# Bus_and_display.net
KiCad netlist of a schematic drawn in Altium Designer
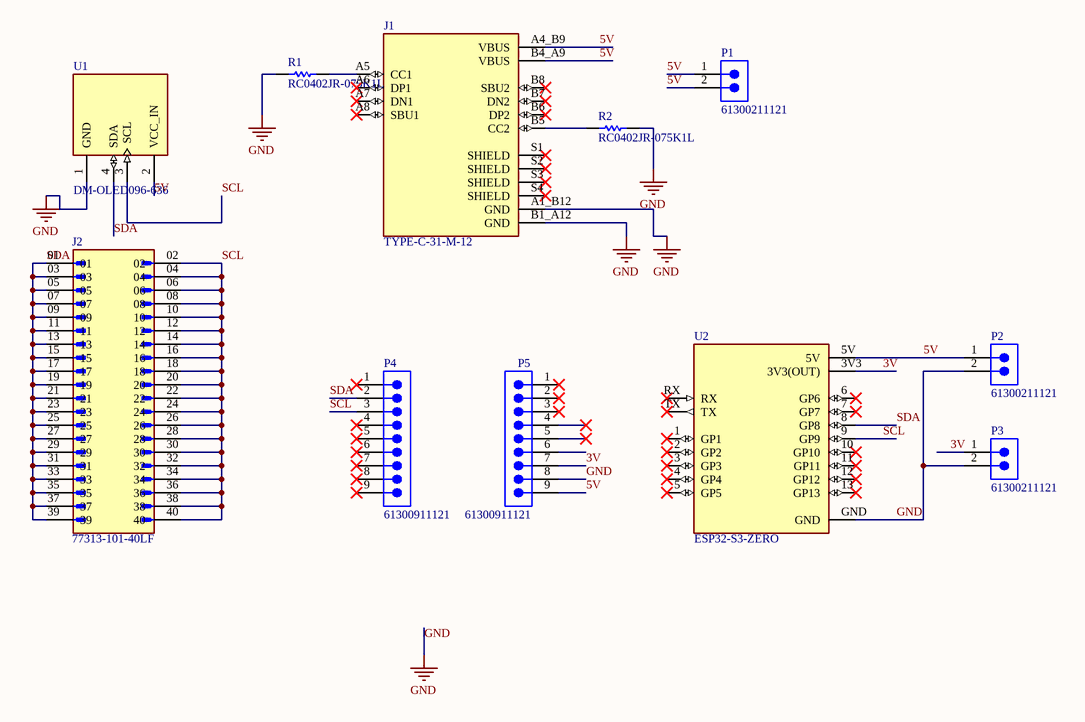
[diagram p0: Bus_and_display.SchDoc]

(export (version "E")
  (design (tool "Eeschema 10.0.6"))
  (components
    (comp (ref "J1")
      (value "TYPE-C-31-M-12")
      (footprint "HRO_TYPE-C-31-M-12")
      (description "USB Connectors 24 Receptacle 1 8.94*7.3mm RoHS")
      (fields (field (name "MF") "HRO Electronics Co., Ltd."))
      (libsource (lib "TYPE-C-31-M-12") (part "TYPE-C-31-M-12"))
    )
    (comp (ref "J2")
      (value "77313-101-40LF")
      (footprint "AMPHENOL_77313-101-40LF")
      (fields (field (name "MF") "Amphenol"))
      (libsource (lib "77313-101-40LF") (part "77313-101-40LF"))
    )
    (comp (ref "P1")
      (value "61300211121")
      (footprint "61300211121")
      (description "THT Vertical Pin Header WR-PHD, Pitch 2.54 mm, Single Row, 2 pins")
      (libsource (lib "Altium Content Vault") (part "Header_Male_1R_02P"))
    )
    (comp (ref "P2")
      (value "61300211121")
      (footprint "61300211121")
      (description "THT Vertical Pin Header WR-PHD, Pitch 2.54 mm, Single Row, 2 pins")
      (libsource (lib "Altium Content Vault") (part "Header_Male_1R_02P"))
    )
    (comp (ref "P3")
      (value "61300211121")
      (footprint "61300211121")
      (description "THT Vertical Pin Header WR-PHD, Pitch 2.54 mm, Single Row, 2 pins")
      (libsource (lib "Altium Content Vault") (part "Header_Male_1R_02P"))
    )
    (comp (ref "P4")
      (value "61300911121")
      (footprint "61300911121")
      (description "THT Vertical Pin Header WR-PHD, Pitch 2.54 mm, Single Row, 9 pins")
      (libsource (lib "Altium Content Vault") (part "Header_Male_1R_09P"))
    )
    (comp (ref "P5")
      (value "61300911121")
      (footprint "61300911121")
      (description "THT Vertical Pin Header WR-PHD, Pitch 2.54 mm, Single Row, 9 pins")
      (libsource (lib "Altium Content Vault") (part "Header_Male_1R_09P"))
    )
    (comp (ref "R1")
      (value "RC0402JR-075K1L")
      (footprint "RESC1005X40X25ML05T10")
      (fields (field (name "MANUFACTURER") "Yageo / Phycomp"))
      (libsource (lib "Altium Content Vault") (part "RES"))
    )
    (comp (ref "R2")
      (value "RC0402JR-075K1L")
      (footprint "RESC1005X40X25ML05T10")
      (fields (field (name "MANUFACTURER") "Yageo / Phycomp"))
      (libsource (lib "Altium Content Vault") (part "RES"))
    )
    (comp (ref "U1")
      (value "DM-OLED096-636")
      (footprint "MODULE_DM-OLED096-636")
      (description "0.96â€ 128 X 64 MONOCHROME GRAPHIC OLED DISPLAY MODULE - I2C")
      (fields (field (name "MF") "Display Module"))
      (libsource (lib "DM-OLED096-636") (part "DM-OLED096-636"))
    )
    (comp (ref "U2")
      (value "ESP32-S3-ZERO")
      (footprint "MODULE_ESP32-S3-ZERO")
      (fields (field (name "MF") "Waveshare Electronics") (field (name "MP") "ESP32-S3-Zero"))
      (libsource (lib "ESP32-S3-ZERO") (part "ESP32-S3-ZERO"))
    )
  )
  (nets
    (net (code "1") (name "/3V") (class "Default")
      (node (ref "P3") (pin "1") (pinfunction "1_1") (pintype "passive"))
      (node (ref "P5") (pin "7") (pinfunction "7_7") (pintype "passive"))
      (node (ref "U2") (pin "3V3") (pinfunction "3V3(OUT)_3V3") (pintype "power_in"))
    )
    (net (code "2") (name "/5V") (class "Default")
      (node (ref "J1") (pin "A4_B9") (pinfunction "VBUS_A4_B9") (pintype "power_in"))
      (node (ref "J1") (pin "B4_A9") (pinfunction "VBUS_B4_A9") (pintype "power_in"))
      (node (ref "P1") (pin "1") (pinfunction "1_1") (pintype "passive"))
      (node (ref "P1") (pin "2") (pinfunction "2_2") (pintype "passive"))
      (node (ref "P2") (pin "1") (pinfunction "1_1") (pintype "passive"))
      (node (ref "P5") (pin "9") (pinfunction "9_9") (pintype "passive"))
      (node (ref "U1") (pin "2") (pinfunction "VCC_IN_2") (pintype "power_in"))
      (node (ref "U2") (pin "5V") (pinfunction "5V_5V") (pintype "power_in"))
    )
    (net (code "3") (name "/SCL") (class "Default")
      (node (ref "J2") (pin "02") (pinfunction "02_02") (pintype "passive"))
      (node (ref "J2") (pin "04") (pinfunction "04_04") (pintype "passive"))
      (node (ref "J2") (pin "06") (pinfunction "06_06") (pintype "passive"))
      (node (ref "J2") (pin "08") (pinfunction "08_08") (pintype "passive"))
      (node (ref "J2") (pin "10") (pinfunction "10_10") (pintype "passive"))
      (node (ref "J2") (pin "12") (pinfunction "12_12") (pintype "passive"))
      (node (ref "J2") (pin "14") (pinfunction "14_14") (pintype "passive"))
      (node (ref "J2") (pin "16") (pinfunction "16_16") (pintype "passive"))
      (node (ref "J2") (pin "18") (pinfunction "18_18") (pintype "passive"))
      (node (ref "J2") (pin "20") (pinfunction "20_20") (pintype "passive"))
      (node (ref "J2") (pin "22") (pinfunction "22_22") (pintype "passive"))
      (node (ref "J2") (pin "24") (pinfunction "24_24") (pintype "passive"))
      (node (ref "J2") (pin "26") (pinfunction "26_26") (pintype "passive"))
      (node (ref "J2") (pin "28") (pinfunction "28_28") (pintype "passive"))
      (node (ref "J2") (pin "30") (pinfunction "30_30") (pintype "passive"))
      (node (ref "J2") (pin "32") (pinfunction "32_32") (pintype "passive"))
      (node (ref "J2") (pin "34") (pinfunction "34_34") (pintype "passive"))
      (node (ref "J2") (pin "36") (pinfunction "36_36") (pintype "passive"))
      (node (ref "J2") (pin "38") (pinfunction "38_38") (pintype "passive"))
      (node (ref "J2") (pin "40") (pinfunction "40_40") (pintype "passive"))
      (node (ref "P4") (pin "3") (pinfunction "3_3") (pintype "passive"))
      (node (ref "U1") (pin "3") (pinfunction "SCL_3") (pintype "input"))
      (node (ref "U2") (pin "9") (pinfunction "GP9_9") (pintype "bidirectional"))
    )
    (net (code "4") (name "/SDA") (class "Default")
      (node (ref "J2") (pin "01") (pinfunction "01_01") (pintype "passive"))
      (node (ref "J2") (pin "03") (pinfunction "03_03") (pintype "passive"))
      (node (ref "J2") (pin "05") (pinfunction "05_05") (pintype "passive"))
      (node (ref "J2") (pin "07") (pinfunction "07_07") (pintype "passive"))
      (node (ref "J2") (pin "09") (pinfunction "09_09") (pintype "passive"))
      (node (ref "J2") (pin "11") (pinfunction "11_11") (pintype "passive"))
      (node (ref "J2") (pin "13") (pinfunction "13_13") (pintype "passive"))
      (node (ref "J2") (pin "15") (pinfunction "15_15") (pintype "passive"))
      (node (ref "J2") (pin "17") (pinfunction "17_17") (pintype "passive"))
      (node (ref "J2") (pin "19") (pinfunction "19_19") (pintype "passive"))
      (node (ref "J2") (pin "21") (pinfunction "21_21") (pintype "passive"))
      (node (ref "J2") (pin "23") (pinfunction "23_23") (pintype "passive"))
      (node (ref "J2") (pin "25") (pinfunction "25_25") (pintype "passive"))
      (node (ref "J2") (pin "27") (pinfunction "27_27") (pintype "passive"))
      (node (ref "J2") (pin "29") (pinfunction "29_29") (pintype "passive"))
      (node (ref "J2") (pin "31") (pinfunction "31_31") (pintype "passive"))
      (node (ref "J2") (pin "33") (pinfunction "33_33") (pintype "passive"))
      (node (ref "J2") (pin "35") (pinfunction "35_35") (pintype "passive"))
      (node (ref "J2") (pin "37") (pinfunction "37_37") (pintype "passive"))
      (node (ref "J2") (pin "39") (pinfunction "39_39") (pintype "passive"))
      (node (ref "P4") (pin "2") (pinfunction "2_2") (pintype "passive"))
      (node (ref "U1") (pin "4") (pinfunction "SDA_4") (pintype "bidirectional"))
      (node (ref "U2") (pin "8") (pinfunction "GP8_8") (pintype "bidirectional"))
    )
    (net (code "5") (name "GND") (class "Default")
      (node (ref "J1") (pin "A1_B12") (pinfunction "GND_A1_B12") (pintype "power_in"))
      (node (ref "J1") (pin "B1_A12") (pinfunction "GND_B1_A12") (pintype "power_in"))
      (node (ref "P2") (pin "2") (pinfunction "2_2") (pintype "passive"))
      (node (ref "P3") (pin "2") (pinfunction "2_2") (pintype "passive"))
      (node (ref "P5") (pin "8") (pinfunction "8_8") (pintype "passive"))
      (node (ref "R1") (pin "1") (pinfunction "1_1") (pintype "passive"))
      (node (ref "R2") (pin "2") (pinfunction "2_2") (pintype "passive"))
      (node (ref "U1") (pin "1") (pinfunction "GND_1") (pintype "power_in"))
      (node (ref "U2") (pin "GND") (pinfunction "GND_GND") (pintype "power_in"))
    )
    (net (code "6") (name "Net-(J1-CC1)") (class "Default")
      (node (ref "J1") (pin "A5") (pinfunction "CC1_A5") (pintype "bidirectional"))
      (node (ref "R1") (pin "2") (pinfunction "2_2") (pintype "passive"))
    )
    (net (code "7") (name "Net-(J1-CC2)") (class "Default")
      (node (ref "J1") (pin "B5") (pinfunction "CC2_B5") (pintype "bidirectional"))
      (node (ref "R2") (pin "1") (pinfunction "1_1") (pintype "passive"))
    )
    (net (code "8") (name "unconnected-(J1-DN1-PadA7)") (class "Default")
      (node (ref "J1") (pin "A7") (pinfunction "DN1_A7") (pintype "bidirectional+no_connect"))
    )
    (net (code "9") (name "unconnected-(J1-DN2-PadB7)") (class "Default")
      (node (ref "J1") (pin "B7") (pinfunction "DN2_B7") (pintype "bidirectional+no_connect"))
    )
    (net (code "10") (name "unconnected-(J1-DP1-PadA6)") (class "Default")
      (node (ref "J1") (pin "A6") (pinfunction "DP1_A6") (pintype "bidirectional+no_connect"))
    )
    (net (code "11") (name "unconnected-(J1-DP2-PadB6)") (class "Default")
      (node (ref "J1") (pin "B6") (pinfunction "DP2_B6") (pintype "bidirectional+no_connect"))
    )
    (net (code "12") (name "unconnected-(J1-SBU1-PadA8)") (class "Default")
      (node (ref "J1") (pin "A8") (pinfunction "SBU1_A8") (pintype "bidirectional+no_connect"))
    )
    (net (code "13") (name "unconnected-(J1-SBU2-PadB8)") (class "Default")
      (node (ref "J1") (pin "B8") (pinfunction "SBU2_B8") (pintype "bidirectional+no_connect"))
    )
    (net (code "14") (name "unconnected-(J1-SHIELD-PadS1)") (class "Default")
      (node (ref "J1") (pin "S1") (pinfunction "SHIELD_S1") (pintype "passive+no_connect"))
    )
    (net (code "15") (name "unconnected-(J1-SHIELD-PadS2)") (class "Default")
      (node (ref "J1") (pin "S2") (pinfunction "SHIELD_S2") (pintype "passive+no_connect"))
    )
    (net (code "16") (name "unconnected-(J1-SHIELD-PadS3)") (class "Default")
      (node (ref "J1") (pin "S3") (pinfunction "SHIELD_S3") (pintype "passive+no_connect"))
    )
    (net (code "17") (name "unconnected-(J1-SHIELD-PadS4)") (class "Default")
      (node (ref "J1") (pin "S4") (pinfunction "SHIELD_S4") (pintype "passive+no_connect"))
    )
    (net (code "18") (name "unconnected-(P4-Pad1)") (class "Default")
      (node (ref "P4") (pin "1") (pinfunction "1_1") (pintype "passive+no_connect"))
    )
    (net (code "19") (name "unconnected-(P4-Pad4)") (class "Default")
      (node (ref "P4") (pin "4") (pinfunction "4_4") (pintype "passive+no_connect"))
    )
    (net (code "20") (name "unconnected-(P4-Pad5)") (class "Default")
      (node (ref "P4") (pin "5") (pinfunction "5_5") (pintype "passive+no_connect"))
    )
    (net (code "21") (name "unconnected-(P4-Pad6)") (class "Default")
      (node (ref "P4") (pin "6") (pinfunction "6_6") (pintype "passive+no_connect"))
    )
    (net (code "22") (name "unconnected-(P4-Pad7)") (class "Default")
      (node (ref "P4") (pin "7") (pinfunction "7_7") (pintype "passive+no_connect"))
    )
    (net (code "23") (name "unconnected-(P4-Pad8)") (class "Default")
      (node (ref "P4") (pin "8") (pinfunction "8_8") (pintype "passive+no_connect"))
    )
    (net (code "24") (name "unconnected-(P4-Pad9)") (class "Default")
      (node (ref "P4") (pin "9") (pinfunction "9_9") (pintype "passive+no_connect"))
    )
    (net (code "25") (name "unconnected-(P5-Pad1)") (class "Default")
      (node (ref "P5") (pin "1") (pinfunction "1_1") (pintype "passive+no_connect"))
    )
    (net (code "26") (name "unconnected-(P5-Pad2)") (class "Default")
      (node (ref "P5") (pin "2") (pinfunction "2_2") (pintype "passive+no_connect"))
    )
    (net (code "27") (name "unconnected-(P5-Pad3)") (class "Default")
      (node (ref "P5") (pin "3") (pinfunction "3_3") (pintype "passive+no_connect"))
    )
    (net (code "28") (name "unconnected-(P5-Pad4)") (class "Default")
      (node (ref "P5") (pin "4") (pinfunction "4_4") (pintype "passive+no_connect"))
    )
    (net (code "29") (name "unconnected-(P5-Pad5)") (class "Default")
      (node (ref "P5") (pin "5") (pinfunction "5_5") (pintype "passive+no_connect"))
    )
    (net (code "30") (name "unconnected-(P5-Pad6)") (class "Default")
      (node (ref "P5") (pin "6") (pinfunction "6_6") (pintype "passive"))
    )
    (net (code "31") (name "unconnected-(U2-GP1-Pad1)") (class "Default")
      (node (ref "U2") (pin "1") (pinfunction "GP1_1") (pintype "bidirectional+no_connect"))
    )
    (net (code "32") (name "unconnected-(U2-GP2-Pad2)") (class "Default")
      (node (ref "U2") (pin "2") (pinfunction "GP2_2") (pintype "bidirectional+no_connect"))
    )
    (net (code "33") (name "unconnected-(U2-GP3-Pad3)") (class "Default")
      (node (ref "U2") (pin "3") (pinfunction "GP3_3") (pintype "bidirectional+no_connect"))
    )
    (net (code "34") (name "unconnected-(U2-GP4-Pad4)") (class "Default")
      (node (ref "U2") (pin "4") (pinfunction "GP4_4") (pintype "bidirectional+no_connect"))
    )
    (net (code "35") (name "unconnected-(U2-GP5-Pad5)") (class "Default")
      (node (ref "U2") (pin "5") (pinfunction "GP5_5") (pintype "bidirectional+no_connect"))
    )
    (net (code "36") (name "unconnected-(U2-GP6-Pad6)") (class "Default")
      (node (ref "U2") (pin "6") (pinfunction "GP6_6") (pintype "bidirectional+no_connect"))
    )
    (net (code "37") (name "unconnected-(U2-GP7-Pad7)") (class "Default")
      (node (ref "U2") (pin "7") (pinfunction "GP7_7") (pintype "bidirectional+no_connect"))
    )
    (net (code "38") (name "unconnected-(U2-GP10-Pad10)") (class "Default")
      (node (ref "U2") (pin "10") (pinfunction "GP10_10") (pintype "bidirectional+no_connect"))
    )
    (net (code "39") (name "unconnected-(U2-GP11-Pad11)") (class "Default")
      (node (ref "U2") (pin "11") (pinfunction "GP11_11") (pintype "bidirectional+no_connect"))
    )
    (net (code "40") (name "unconnected-(U2-GP12-Pad12)") (class "Default")
      (node (ref "U2") (pin "12") (pinfunction "GP12_12") (pintype "bidirectional+no_connect"))
    )
    (net (code "41") (name "unconnected-(U2-GP13-Pad13)") (class "Default")
      (node (ref "U2") (pin "13") (pinfunction "GP13_13") (pintype "bidirectional+no_connect"))
    )
    (net (code "42") (name "unconnected-(U2-PadRX)") (class "Default")
      (node (ref "U2") (pin "RX") (pinfunction "RX_RX") (pintype "input+no_connect"))
    )
    (net (code "43") (name "unconnected-(U2-PadTX)") (class "Default")
      (node (ref "U2") (pin "TX") (pinfunction "TX_TX") (pintype "output+no_connect"))
    )
  )
)
